# breakoutBoard_03.net
KiCad netlist of a schematic drawn in EAGLE
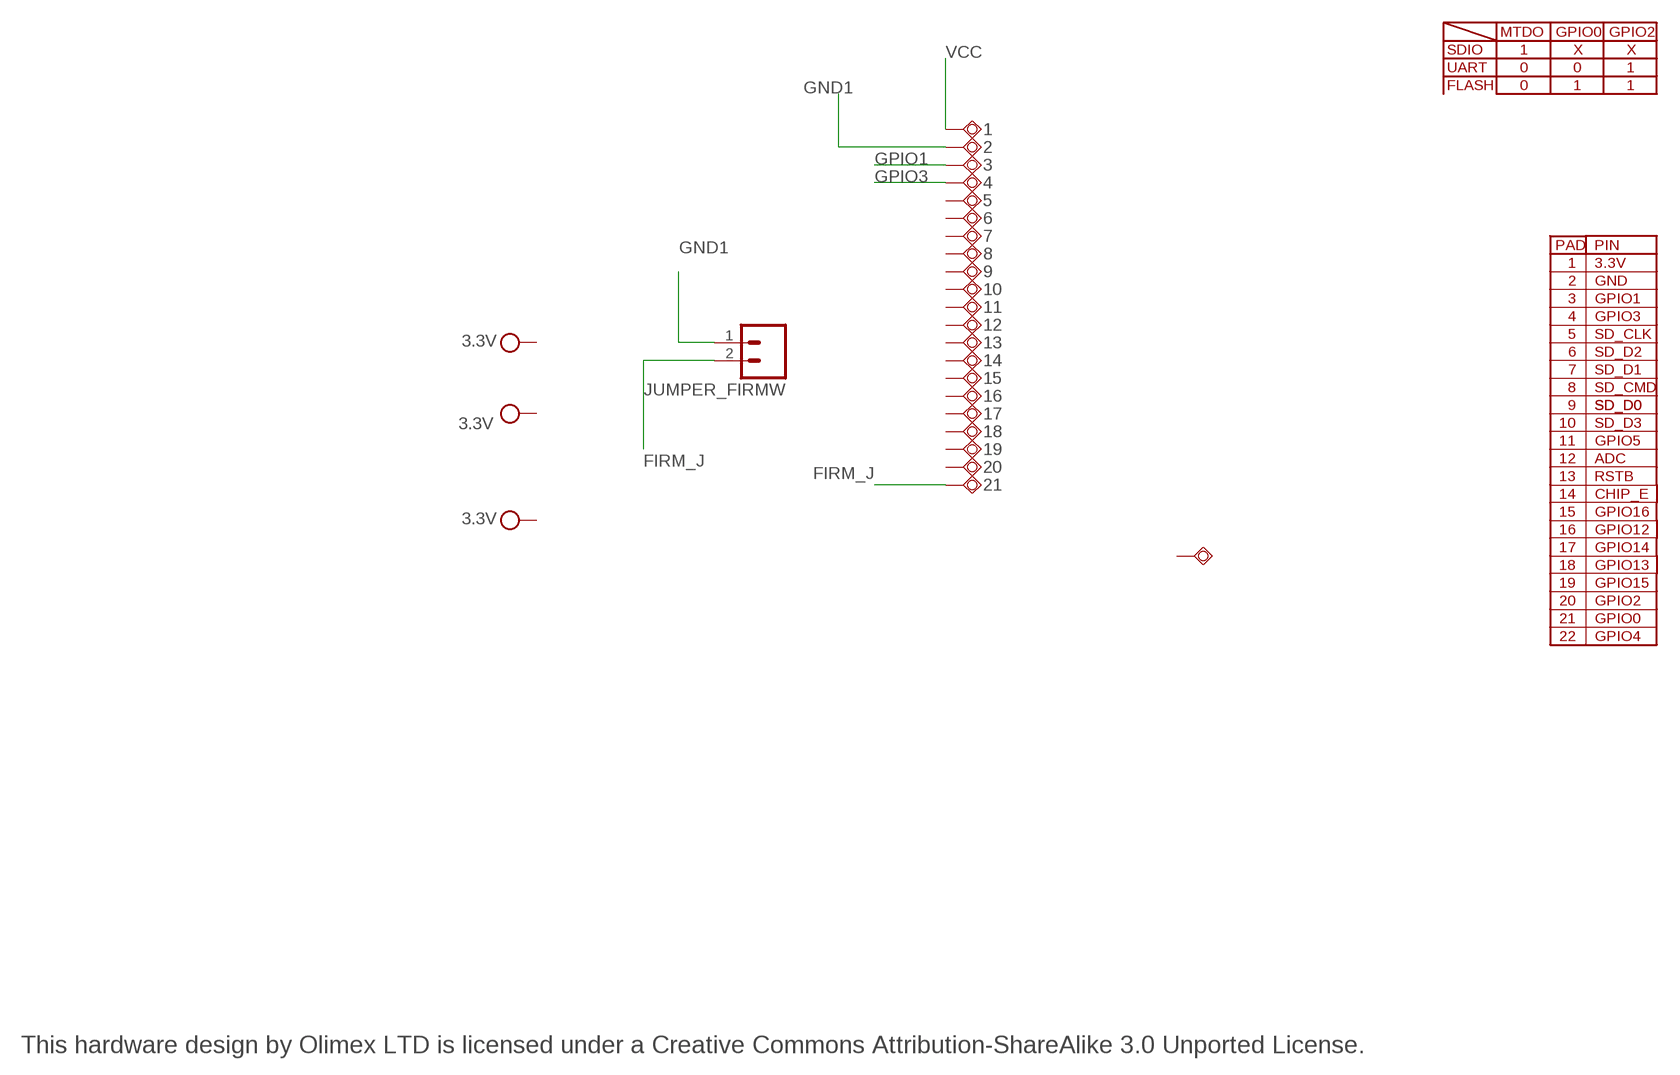
[diagram p0: schematic, sheet 1, part 1 of 2]
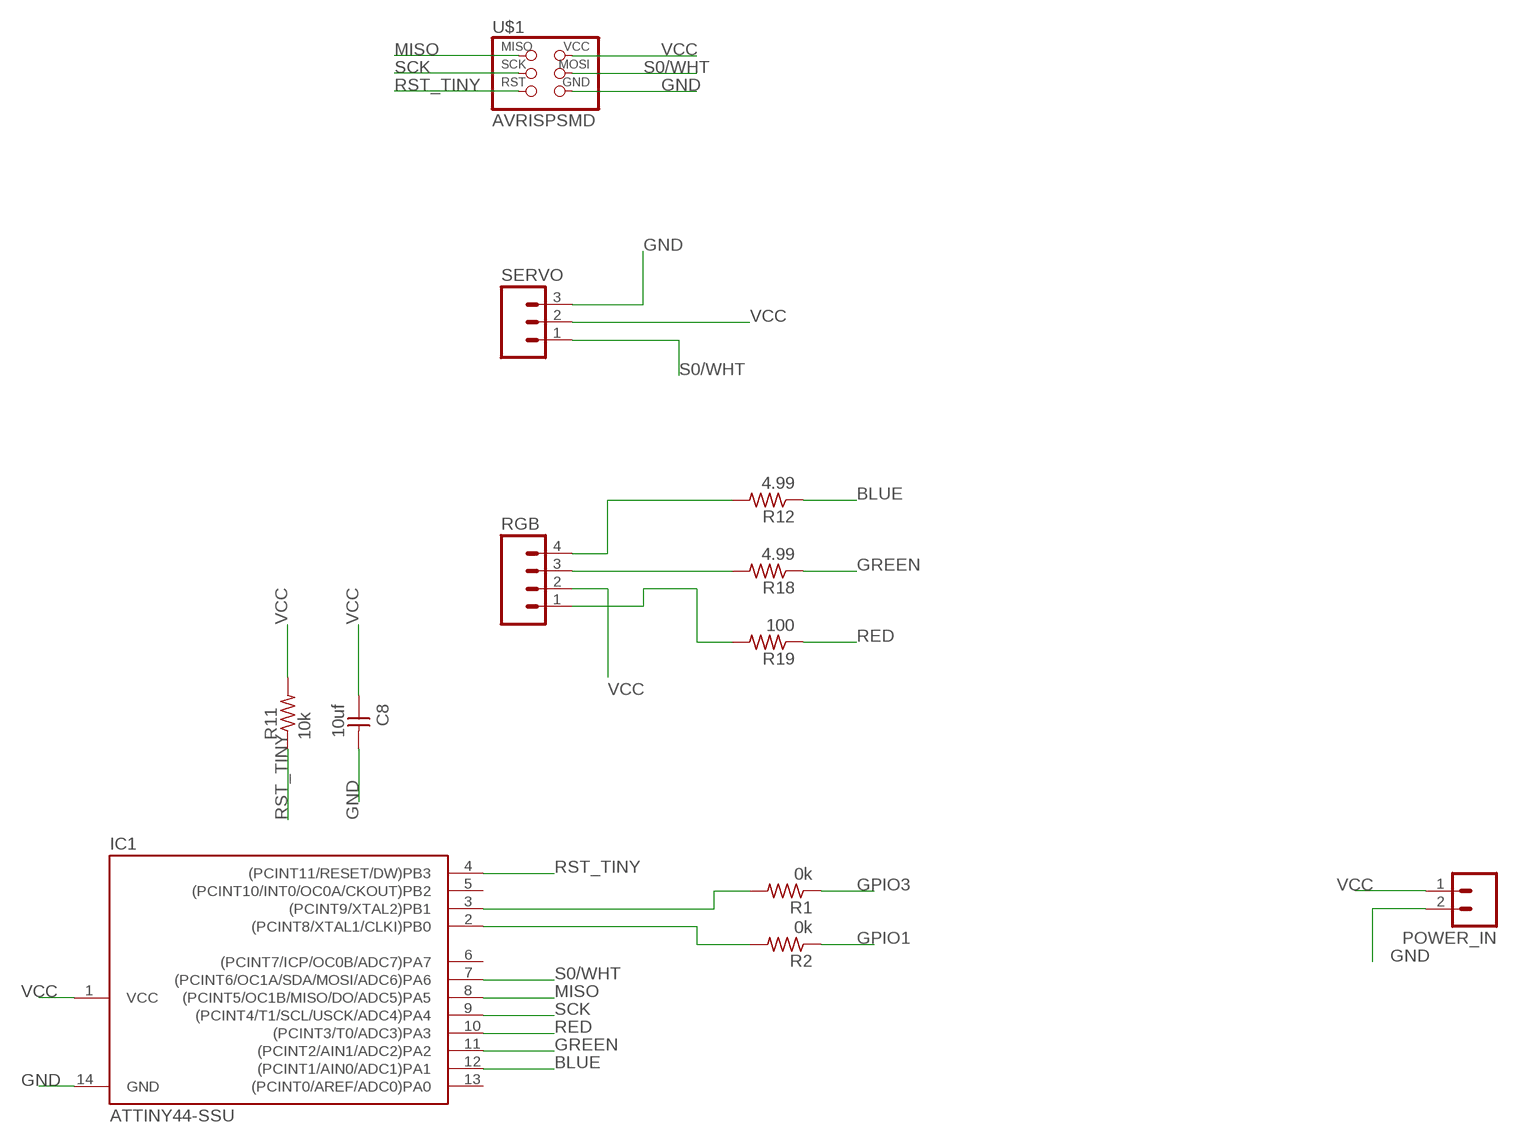
[diagram p1: schematic, sheet 1, part 2 of 2]

(export (version "E")
  (design (tool "Eeschema 10.0.6"))
  (components
    (comp (ref "1")
      (value "TESTPAD8")
      (footprint "eagle-import:TESTPAD50_80")
      (libsource (lib "eagle-import") (part "TESTPAD8"))
    )
    (comp (ref "2")
      (value "TESTPAD8")
      (footprint "eagle-import:TESTPAD50_80")
      (libsource (lib "eagle-import") (part "TESTPAD8"))
    )
    (comp (ref "3")
      (value "TESTPAD8")
      (footprint "eagle-import:TESTPAD50_80")
      (libsource (lib "eagle-import") (part "TESTPAD8"))
    )
    (comp (ref "4")
      (value "TESTPAD8")
      (footprint "eagle-import:TESTPAD50_80")
      (libsource (lib "eagle-import") (part "TESTPAD8"))
    )
    (comp (ref "5")
      (value "TESTPAD8")
      (footprint "eagle-import:TESTPAD50_80")
      (libsource (lib "eagle-import") (part "TESTPAD8"))
    )
    (comp (ref "6")
      (value "TESTPAD8")
      (footprint "eagle-import:TESTPAD50_80")
      (libsource (lib "eagle-import") (part "TESTPAD8"))
    )
    (comp (ref "7")
      (value "TESTPAD8")
      (footprint "eagle-import:TESTPAD50_80")
      (libsource (lib "eagle-import") (part "TESTPAD8"))
    )
    (comp (ref "8")
      (value "TESTPAD8")
      (footprint "eagle-import:TESTPAD50_80")
      (libsource (lib "eagle-import") (part "TESTPAD8"))
    )
    (comp (ref "9")
      (value "TESTPAD8")
      (footprint "eagle-import:TESTPAD50_80")
      (libsource (lib "eagle-import") (part "TESTPAD8"))
    )
    (comp (ref "10")
      (value "TESTPAD8")
      (footprint "eagle-import:TESTPAD50_80")
      (libsource (lib "eagle-import") (part "TESTPAD8"))
    )
    (comp (ref "11")
      (value "TESTPAD8")
      (footprint "eagle-import:TESTPAD50_80")
      (libsource (lib "eagle-import") (part "TESTPAD8"))
    )
    (comp (ref "12")
      (value "TESTPAD8")
      (footprint "eagle-import:TESTPAD50_80")
      (libsource (lib "eagle-import") (part "TESTPAD8"))
    )
    (comp (ref "13")
      (value "TESTPAD8")
      (footprint "eagle-import:TESTPAD50_80")
      (libsource (lib "eagle-import") (part "TESTPAD8"))
    )
    (comp (ref "14")
      (value "TESTPAD8")
      (footprint "eagle-import:TESTPAD50_80")
      (libsource (lib "eagle-import") (part "TESTPAD8"))
    )
    (comp (ref "15")
      (value "TESTPAD8")
      (footprint "eagle-import:TESTPAD50_80")
      (libsource (lib "eagle-import") (part "TESTPAD8"))
    )
    (comp (ref "16")
      (value "TESTPAD8")
      (footprint "eagle-import:TESTPAD50_80")
      (libsource (lib "eagle-import") (part "TESTPAD8"))
    )
    (comp (ref "17")
      (value "TESTPAD8")
      (footprint "eagle-import:TESTPAD50_80")
      (libsource (lib "eagle-import") (part "TESTPAD8"))
    )
    (comp (ref "18")
      (value "TESTPAD8")
      (footprint "eagle-import:TESTPAD50_80")
      (libsource (lib "eagle-import") (part "TESTPAD8"))
    )
    (comp (ref "19")
      (value "TESTPAD8")
      (footprint "eagle-import:TESTPAD50_80")
      (libsource (lib "eagle-import") (part "TESTPAD8"))
    )
    (comp (ref "20")
      (value "TESTPAD8")
      (footprint "eagle-import:TESTPAD50_80")
      (libsource (lib "eagle-import") (part "TESTPAD8"))
    )
    (comp (ref "21")
      (value "TESTPAD8")
      (footprint "eagle-import:TESTPAD50_80")
      (libsource (lib "eagle-import") (part "TESTPAD8"))
    )
    (comp (ref "22")
      (value "TESTPAD8")
      (footprint "eagle-import:TESTPAD50_80")
      (libsource (lib "eagle-import") (part "TESTPAD8"))
    )
    (comp (ref "C8")
      (value "10uf")
      (footprint "eagle-import:1206")
      (libsource (lib "eagle-import") (part "UNPOLARIZED_CAPACITOR1206"))
    )
    (comp (ref "IC1")
      (value "ATTINY44-SSU")
      (footprint "eagle-import:SOIC14")
      (libsource (lib "eagle-import") (part "ATTINY44-SSU"))
    )
    (comp (ref "JUMPER_FIRMW")
      (value "M02LOCK_LONGPADS")
      (footprint "eagle-import:1X02_LOCK_LONGPADS")
      (libsource (lib "eagle-import") (part "M02LOCK_LONGPADS"))
    )
    (comp (ref "POWER_IN")
      (value "M02LOCK_LONGPADS")
      (footprint "eagle-import:1X02_LOCK_LONGPADS")
      (libsource (lib "eagle-import") (part "M02LOCK_LONGPADS"))
    )
    (comp (ref "R1")
      (value "0k")
      (footprint "eagle-import:1206")
      (libsource (lib "eagle-import") (part "RESISTOR1206"))
    )
    (comp (ref "R2")
      (value "0k")
      (footprint "eagle-import:1206")
      (libsource (lib "eagle-import") (part "RESISTOR1206"))
    )
    (comp (ref "R11")
      (value "10k")
      (footprint "eagle-import:1206")
      (libsource (lib "eagle-import") (part "RESISTOR1206"))
    )
    (comp (ref "R12")
      (value "4.99")
      (footprint "eagle-import:1206")
      (libsource (lib "eagle-import") (part "RESISTOR1206"))
    )
    (comp (ref "R18")
      (value "4.99")
      (footprint "eagle-import:1206")
      (libsource (lib "eagle-import") (part "RESISTOR1206"))
    )
    (comp (ref "R19")
      (value "100")
      (footprint "eagle-import:1206")
      (libsource (lib "eagle-import") (part "RESISTOR1206"))
    )
    (comp (ref "RGB")
      (value "M04LONGPADS")
      (footprint "eagle-import:1X04_LONGPADS")
      (libsource (lib "eagle-import") (part "M04LONGPADS"))
    )
    (comp (ref "SERVO")
      (value "M03LOCK_LONGPADS")
      (footprint "eagle-import:1X03_LOCK_LONGPADS")
      (libsource (lib "eagle-import") (part "M03LOCK_LONGPADS"))
    )
    (comp (ref "U$1")
      (value "AVRISPSMD")
      (footprint "eagle-import:2X03SMD")
      (libsource (lib "eagle-import") (part "AVRISPSMD"))
    )
  )
  (nets
    (net (code "1") (name "/BLUE") (class "Default")
      (node (ref "IC1") (pin "12") (pinfunction "(PCINT1/AIN0/ADC1)PA1_12") (pintype "bidirectional"))
      (node (ref "R12") (pin "1") (pinfunction "1_1") (pintype "passive"))
    )
    (net (code "2") (name "/FIRM_J") (class "Default")
      (node (ref "21") (pin "P$1") (pinfunction "PP_P$1") (pintype "passive"))
      (node (ref "JUMPER_FIRMW") (pin "2") (pinfunction "2_2") (pintype "passive"))
    )
    (net (code "3") (name "/GND") (class "Default")
      (node (ref "C8") (pin "2") (pinfunction "2_2") (pintype "passive"))
      (node (ref "IC1") (pin "14") (pinfunction "GND_14") (pintype "power_in"))
      (node (ref "POWER_IN") (pin "2") (pinfunction "2_2") (pintype "passive"))
      (node (ref "SERVO") (pin "3") (pinfunction "3_3") (pintype "passive"))
      (node (ref "U$1") (pin "6") (pinfunction "GND_6") (pintype "passive"))
    )
    (net (code "4") (name "/GND1") (class "Default")
      (node (ref "2") (pin "P$1") (pinfunction "PP_P$1") (pintype "passive"))
      (node (ref "JUMPER_FIRMW") (pin "1") (pinfunction "1_1") (pintype "passive"))
    )
    (net (code "5") (name "/GPIO1") (class "Default")
      (node (ref "3") (pin "P$1") (pinfunction "PP_P$1") (pintype "passive"))
      (node (ref "R2") (pin "1") (pinfunction "1_1") (pintype "passive"))
    )
    (net (code "6") (name "/GPIO3") (class "Default")
      (node (ref "4") (pin "P$1") (pinfunction "PP_P$1") (pintype "passive"))
      (node (ref "R1") (pin "1") (pinfunction "1_1") (pintype "passive"))
    )
    (net (code "7") (name "/GREEN") (class "Default")
      (node (ref "IC1") (pin "11") (pinfunction "(PCINT2/AIN1/ADC2)PA2_11") (pintype "bidirectional"))
      (node (ref "R18") (pin "1") (pinfunction "1_1") (pintype "passive"))
    )
    (net (code "8") (name "/MISO") (class "Default")
      (node (ref "IC1") (pin "8") (pinfunction "(PCINT5/OC1B/MISO/DO/ADC5)PA5_8") (pintype "bidirectional"))
      (node (ref "U$1") (pin "1") (pinfunction "MISO_1") (pintype "passive"))
    )
    (net (code "9") (name "/RED") (class "Default")
      (node (ref "IC1") (pin "10") (pinfunction "(PCINT3/T0/ADC3)PA3_10") (pintype "bidirectional"))
      (node (ref "R19") (pin "1") (pinfunction "1_1") (pintype "passive"))
    )
    (net (code "10") (name "/RST_TINY") (class "Default")
      (node (ref "IC1") (pin "4") (pinfunction "(PCINT11/RESET/DW)PB3_4") (pintype "bidirectional"))
      (node (ref "R11") (pin "1") (pinfunction "1_1") (pintype "passive"))
      (node (ref "U$1") (pin "5") (pinfunction "RST_5") (pintype "passive"))
    )
    (net (code "11") (name "/S0{slash}WHT") (class "Default")
      (node (ref "IC1") (pin "7") (pinfunction "(PCINT6/OC1A/SDA/MOSI/ADC6)PA6_7") (pintype "bidirectional"))
      (node (ref "SERVO") (pin "1") (pinfunction "1_1") (pintype "passive"))
      (node (ref "U$1") (pin "4") (pinfunction "MOSI_4") (pintype "passive"))
    )
    (net (code "12") (name "/SCK") (class "Default")
      (node (ref "IC1") (pin "9") (pinfunction "(PCINT4/T1/SCL/USCK/ADC4)PA4_9") (pintype "bidirectional"))
      (node (ref "U$1") (pin "3") (pinfunction "SCK_3") (pintype "passive"))
    )
    (net (code "13") (name "/VCC") (class "Default")
      (node (ref "1") (pin "P$1") (pinfunction "PP_P$1") (pintype "passive"))
      (node (ref "C8") (pin "1") (pinfunction "1_1") (pintype "passive"))
      (node (ref "IC1") (pin "1") (pinfunction "VCC_1") (pintype "power_in"))
      (node (ref "POWER_IN") (pin "1") (pinfunction "1_1") (pintype "passive"))
      (node (ref "R11") (pin "2") (pinfunction "2_2") (pintype "passive"))
      (node (ref "RGB") (pin "2") (pinfunction "2_2") (pintype "passive"))
      (node (ref "SERVO") (pin "2") (pinfunction "2_2") (pintype "passive"))
      (node (ref "U$1") (pin "2") (pinfunction "VCC_2") (pintype "passive"))
    )
    (net (code "15") (name "Net-(IC1-(PCINT8{slash}XTAL1{slash}CLKI)PB0)") (class "Default")
      (node (ref "IC1") (pin "2") (pinfunction "(PCINT8/XTAL1/CLKI)PB0_2") (pintype "bidirectional"))
      (node (ref "R2") (pin "2") (pinfunction "2_2") (pintype "passive"))
    )
    (net (code "16") (name "Net-(IC1-(PCINT9{slash}XTAL2)PB1)") (class "Default")
      (node (ref "IC1") (pin "3") (pinfunction "(PCINT9/XTAL2)PB1_3") (pintype "bidirectional"))
      (node (ref "R1") (pin "2") (pinfunction "2_2") (pintype "passive"))
    )
    (net (code "17") (name "Net-(R12-Pad2)") (class "Default")
      (node (ref "R12") (pin "2") (pinfunction "2_2") (pintype "passive"))
      (node (ref "RGB") (pin "4") (pinfunction "4_4") (pintype "passive"))
    )
    (net (code "18") (name "Net-(R18-Pad2)") (class "Default")
      (node (ref "R18") (pin "2") (pinfunction "2_2") (pintype "passive"))
      (node (ref "RGB") (pin "3") (pinfunction "3_3") (pintype "passive"))
    )
    (net (code "19") (name "Net-(R19-Pad2)") (class "Default")
      (node (ref "R19") (pin "2") (pinfunction "2_2") (pintype "passive"))
      (node (ref "RGB") (pin "1") (pinfunction "1_1") (pintype "passive"))
    )
    (net (code "20") (name "unconnected-(5-PP-PadP$1)") (class "Default")
      (node (ref "5") (pin "P$1") (pinfunction "PP_P$1") (pintype "passive"))
    )
    (net (code "21") (name "unconnected-(6-PP-PadP$1)") (class "Default")
      (node (ref "6") (pin "P$1") (pinfunction "PP_P$1") (pintype "passive"))
    )
    (net (code "22") (name "unconnected-(7-PP-PadP$1)") (class "Default")
      (node (ref "7") (pin "P$1") (pinfunction "PP_P$1") (pintype "passive"))
    )
    (net (code "23") (name "unconnected-(8-PP-PadP$1)") (class "Default")
      (node (ref "8") (pin "P$1") (pinfunction "PP_P$1") (pintype "passive"))
    )
    (net (code "24") (name "unconnected-(9-PP-PadP$1)") (class "Default")
      (node (ref "9") (pin "P$1") (pinfunction "PP_P$1") (pintype "passive"))
    )
    (net (code "25") (name "unconnected-(10-PP-PadP$1)") (class "Default")
      (node (ref "10") (pin "P$1") (pinfunction "PP_P$1") (pintype "passive"))
    )
    (net (code "26") (name "unconnected-(11-PP-PadP$1)") (class "Default")
      (node (ref "11") (pin "P$1") (pinfunction "PP_P$1") (pintype "passive"))
    )
    (net (code "27") (name "unconnected-(12-PP-PadP$1)") (class "Default")
      (node (ref "12") (pin "P$1") (pinfunction "PP_P$1") (pintype "passive"))
    )
    (net (code "28") (name "unconnected-(13-PP-PadP$1)") (class "Default")
      (node (ref "13") (pin "P$1") (pinfunction "PP_P$1") (pintype "passive"))
    )
    (net (code "29") (name "unconnected-(14-PP-PadP$1)") (class "Default")
      (node (ref "14") (pin "P$1") (pinfunction "PP_P$1") (pintype "passive"))
    )
    (net (code "30") (name "unconnected-(15-PP-PadP$1)") (class "Default")
      (node (ref "15") (pin "P$1") (pinfunction "PP_P$1") (pintype "passive"))
    )
    (net (code "31") (name "unconnected-(16-PP-PadP$1)") (class "Default")
      (node (ref "16") (pin "P$1") (pinfunction "PP_P$1") (pintype "passive"))
    )
    (net (code "32") (name "unconnected-(17-PP-PadP$1)") (class "Default")
      (node (ref "17") (pin "P$1") (pinfunction "PP_P$1") (pintype "passive"))
    )
    (net (code "33") (name "unconnected-(18-PP-PadP$1)") (class "Default")
      (node (ref "18") (pin "P$1") (pinfunction "PP_P$1") (pintype "passive"))
    )
    (net (code "34") (name "unconnected-(19-PP-PadP$1)") (class "Default")
      (node (ref "19") (pin "P$1") (pinfunction "PP_P$1") (pintype "passive"))
    )
    (net (code "35") (name "unconnected-(20-PP-PadP$1)") (class "Default")
      (node (ref "20") (pin "P$1") (pinfunction "PP_P$1") (pintype "passive"))
    )
    (net (code "36") (name "unconnected-(22-PP-PadP$1)") (class "Default")
      (node (ref "22") (pin "P$1") (pinfunction "PP_P$1") (pintype "passive"))
    )
    (net (code "37") (name "unconnected-(IC1-(PCINT0{slash}AREF{slash}ADC0)PA0-Pad13)") (class "Default")
      (node (ref "IC1") (pin "13") (pinfunction "(PCINT0/AREF/ADC0)PA0_13") (pintype "bidirectional"))
    )
    (net (code "38") (name "unconnected-(IC1-(PCINT7{slash}ICP{slash}OC0B{slash}ADC7)PA7-Pad6)") (class "Default")
      (node (ref "IC1") (pin "6") (pinfunction "(PCINT7/ICP/OC0B/ADC7)PA7_6") (pintype "bidirectional"))
    )
    (net (code "39") (name "unconnected-(IC1-(PCINT10{slash}INT0{slash}OC0A{slash}CKOUT)PB2-Pad5)") (class "Default")
      (node (ref "IC1") (pin "5") (pinfunction "(PCINT10/INT0/OC0A/CKOUT)PB2_5") (pintype "bidirectional"))
    )
  )
)
